# ema-module.net
KiCad netlist of a schematic drawn in EAGLE
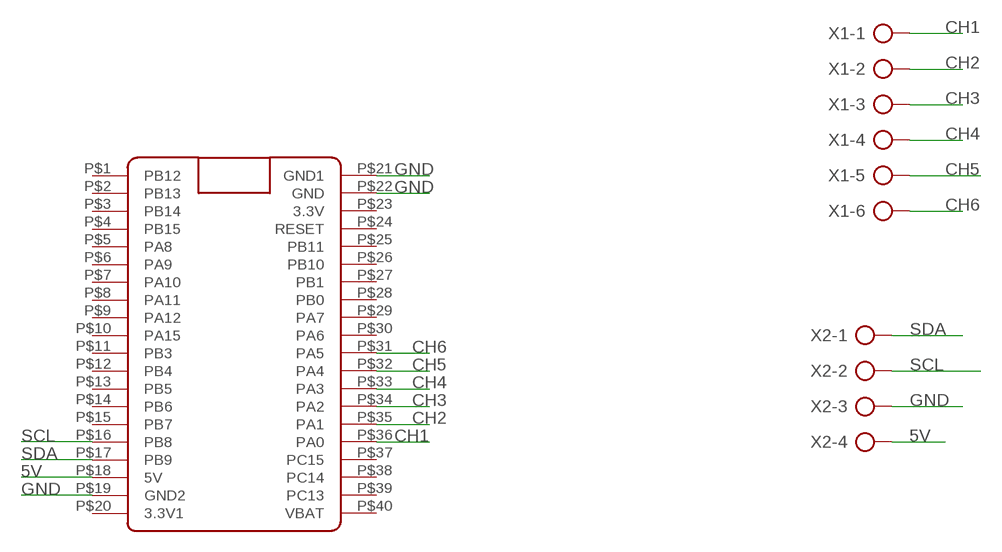
[diagram p0: schematic, sheet 1]

(export (version "E")
  (design (tool "Eeschema 10.0.6"))
  (components
    (comp (ref "U$1")
      (value "BLUE_PILL")
      (footprint "eagle-import:BLUE_PILL")
      (libsource (lib "eagle-import") (part "BLUE_PILL"))
    )
    (comp (ref "X1")
      (value "AK500/6-H")
      (footprint "eagle-import:AK500_6-H")
      (libsource (lib "eagle-import") (part "AK500/6-H"))
    )
    (comp (ref "X2")
      (value "AK500/4-H")
      (footprint "eagle-import:AK500_4-H")
      (libsource (lib "eagle-import") (part "AK500/4-H"))
    )
  )
  (nets
    (net (code "1") (name "/5V") (class "Default")
      (node (ref "U$1") (pin "P$18") (pinfunction "5V_P$18") (pintype "bidirectional"))
      (node (ref "X2") (pin "4") (pinfunction "KL_4") (pintype "passive"))
    )
    (net (code "2") (name "/CH1") (class "Default")
      (node (ref "U$1") (pin "P$36") (pinfunction "PA0_P$36") (pintype "bidirectional"))
      (node (ref "X1") (pin "1") (pinfunction "KL_1") (pintype "passive"))
    )
    (net (code "3") (name "/CH2") (class "Default")
      (node (ref "U$1") (pin "P$35") (pinfunction "PA1_P$35") (pintype "bidirectional"))
      (node (ref "X1") (pin "2") (pinfunction "KL_2") (pintype "passive"))
    )
    (net (code "4") (name "/CH3") (class "Default")
      (node (ref "U$1") (pin "P$34") (pinfunction "PA2_P$34") (pintype "bidirectional"))
      (node (ref "X1") (pin "3") (pinfunction "KL_3") (pintype "passive"))
    )
    (net (code "5") (name "/CH4") (class "Default")
      (node (ref "U$1") (pin "P$33") (pinfunction "PA3_P$33") (pintype "bidirectional"))
      (node (ref "X1") (pin "4") (pinfunction "KL_4") (pintype "passive"))
    )
    (net (code "6") (name "/CH5") (class "Default")
      (node (ref "U$1") (pin "P$32") (pinfunction "PA4_P$32") (pintype "bidirectional"))
      (node (ref "X1") (pin "5") (pinfunction "KL_5") (pintype "passive"))
    )
    (net (code "7") (name "/CH6") (class "Default")
      (node (ref "U$1") (pin "P$31") (pinfunction "PA5_P$31") (pintype "bidirectional"))
      (node (ref "X1") (pin "6") (pinfunction "KL_6") (pintype "passive"))
    )
    (net (code "8") (name "/GND") (class "Default")
      (node (ref "U$1") (pin "P$19") (pinfunction "GND2_P$19") (pintype "bidirectional"))
      (node (ref "U$1") (pin "P$21") (pinfunction "GND1_P$21") (pintype "power_in"))
      (node (ref "U$1") (pin "P$22") (pinfunction "GND_P$22") (pintype "bidirectional"))
      (node (ref "X2") (pin "3") (pinfunction "KL_3") (pintype "passive"))
    )
    (net (code "9") (name "/SCL") (class "Default")
      (node (ref "U$1") (pin "P$16") (pinfunction "PB8_P$16") (pintype "bidirectional"))
      (node (ref "X2") (pin "2") (pinfunction "KL_2") (pintype "passive"))
    )
    (net (code "10") (name "/SDA") (class "Default")
      (node (ref "U$1") (pin "P$17") (pinfunction "PB9_P$17") (pintype "bidirectional"))
      (node (ref "X2") (pin "1") (pinfunction "KL_1") (pintype "passive"))
    )
    (net (code "11") (name "unconnected-(U$1-3.3V-PadP$23)") (class "Default")
      (node (ref "U$1") (pin "P$23") (pinfunction "3.3V_P$23") (pintype "bidirectional"))
    )
    (net (code "12") (name "unconnected-(U$1-3.3V1-PadP$20)") (class "Default")
      (node (ref "U$1") (pin "P$20") (pinfunction "3.3V1_P$20") (pintype "bidirectional"))
    )
    (net (code "13") (name "unconnected-(U$1-PA6-PadP$30)") (class "Default")
      (node (ref "U$1") (pin "P$30") (pinfunction "PA6_P$30") (pintype "bidirectional"))
    )
    (net (code "14") (name "unconnected-(U$1-PA7-PadP$29)") (class "Default")
      (node (ref "U$1") (pin "P$29") (pinfunction "PA7_P$29") (pintype "bidirectional"))
    )
    (net (code "15") (name "unconnected-(U$1-PA8-PadP$5)") (class "Default")
      (node (ref "U$1") (pin "P$5") (pinfunction "PA8_P$5") (pintype "bidirectional"))
    )
    (net (code "16") (name "unconnected-(U$1-PA9-PadP$6)") (class "Default")
      (node (ref "U$1") (pin "P$6") (pinfunction "PA9_P$6") (pintype "bidirectional"))
    )
    (net (code "17") (name "unconnected-(U$1-PA10-PadP$7)") (class "Default")
      (node (ref "U$1") (pin "P$7") (pinfunction "PA10_P$7") (pintype "bidirectional"))
    )
    (net (code "18") (name "unconnected-(U$1-PA11-PadP$8)") (class "Default")
      (node (ref "U$1") (pin "P$8") (pinfunction "PA11_P$8") (pintype "bidirectional"))
    )
    (net (code "19") (name "unconnected-(U$1-PA12-PadP$9)") (class "Default")
      (node (ref "U$1") (pin "P$9") (pinfunction "PA12_P$9") (pintype "bidirectional"))
    )
    (net (code "20") (name "unconnected-(U$1-PA15-PadP$10)") (class "Default")
      (node (ref "U$1") (pin "P$10") (pinfunction "PA15_P$10") (pintype "bidirectional"))
    )
    (net (code "21") (name "unconnected-(U$1-PB0-PadP$28)") (class "Default")
      (node (ref "U$1") (pin "P$28") (pinfunction "PB0_P$28") (pintype "bidirectional"))
    )
    (net (code "22") (name "unconnected-(U$1-PB1-PadP$27)") (class "Default")
      (node (ref "U$1") (pin "P$27") (pinfunction "PB1_P$27") (pintype "bidirectional"))
    )
    (net (code "23") (name "unconnected-(U$1-PB3-PadP$11)") (class "Default")
      (node (ref "U$1") (pin "P$11") (pinfunction "PB3_P$11") (pintype "bidirectional"))
    )
    (net (code "24") (name "unconnected-(U$1-PB4-PadP$12)") (class "Default")
      (node (ref "U$1") (pin "P$12") (pinfunction "PB4_P$12") (pintype "bidirectional"))
    )
    (net (code "25") (name "unconnected-(U$1-PB5-PadP$13)") (class "Default")
      (node (ref "U$1") (pin "P$13") (pinfunction "PB5_P$13") (pintype "bidirectional"))
    )
    (net (code "26") (name "unconnected-(U$1-PB6-PadP$14)") (class "Default")
      (node (ref "U$1") (pin "P$14") (pinfunction "PB6_P$14") (pintype "bidirectional"))
    )
    (net (code "27") (name "unconnected-(U$1-PB7-PadP$15)") (class "Default")
      (node (ref "U$1") (pin "P$15") (pinfunction "PB7_P$15") (pintype "bidirectional"))
    )
    (net (code "28") (name "unconnected-(U$1-PB10-PadP$26)") (class "Default")
      (node (ref "U$1") (pin "P$26") (pinfunction "PB10_P$26") (pintype "bidirectional"))
    )
    (net (code "29") (name "unconnected-(U$1-PB11-PadP$25)") (class "Default")
      (node (ref "U$1") (pin "P$25") (pinfunction "PB11_P$25") (pintype "bidirectional"))
    )
    (net (code "30") (name "unconnected-(U$1-PB12-PadP$1)") (class "Default")
      (node (ref "U$1") (pin "P$1") (pinfunction "PB12_P$1") (pintype "bidirectional"))
    )
    (net (code "31") (name "unconnected-(U$1-PB13-PadP$2)") (class "Default")
      (node (ref "U$1") (pin "P$2") (pinfunction "PB13_P$2") (pintype "bidirectional"))
    )
    (net (code "32") (name "unconnected-(U$1-PB14-PadP$3)") (class "Default")
      (node (ref "U$1") (pin "P$3") (pinfunction "PB14_P$3") (pintype "bidirectional"))
    )
    (net (code "33") (name "unconnected-(U$1-PB15-PadP$4)") (class "Default")
      (node (ref "U$1") (pin "P$4") (pinfunction "PB15_P$4") (pintype "bidirectional"))
    )
    (net (code "34") (name "unconnected-(U$1-PC13-PadP$39)") (class "Default")
      (node (ref "U$1") (pin "P$39") (pinfunction "PC13_P$39") (pintype "bidirectional"))
    )
    (net (code "35") (name "unconnected-(U$1-PC14-PadP$38)") (class "Default")
      (node (ref "U$1") (pin "P$38") (pinfunction "PC14_P$38") (pintype "bidirectional"))
    )
    (net (code "36") (name "unconnected-(U$1-PC15-PadP$37)") (class "Default")
      (node (ref "U$1") (pin "P$37") (pinfunction "PC15_P$37") (pintype "bidirectional"))
    )
    (net (code "37") (name "unconnected-(U$1-RESET-PadP$24)") (class "Default")
      (node (ref "U$1") (pin "P$24") (pinfunction "RESET_P$24") (pintype "bidirectional"))
    )
    (net (code "38") (name "unconnected-(U$1-VBAT-PadP$40)") (class "Default")
      (node (ref "U$1") (pin "P$40") (pinfunction "VBAT_P$40") (pintype "bidirectional"))
    )
  )
)
